# 100kw_dc_motor_controller.net
KiCad netlist of a schematic drawn in EAGLE
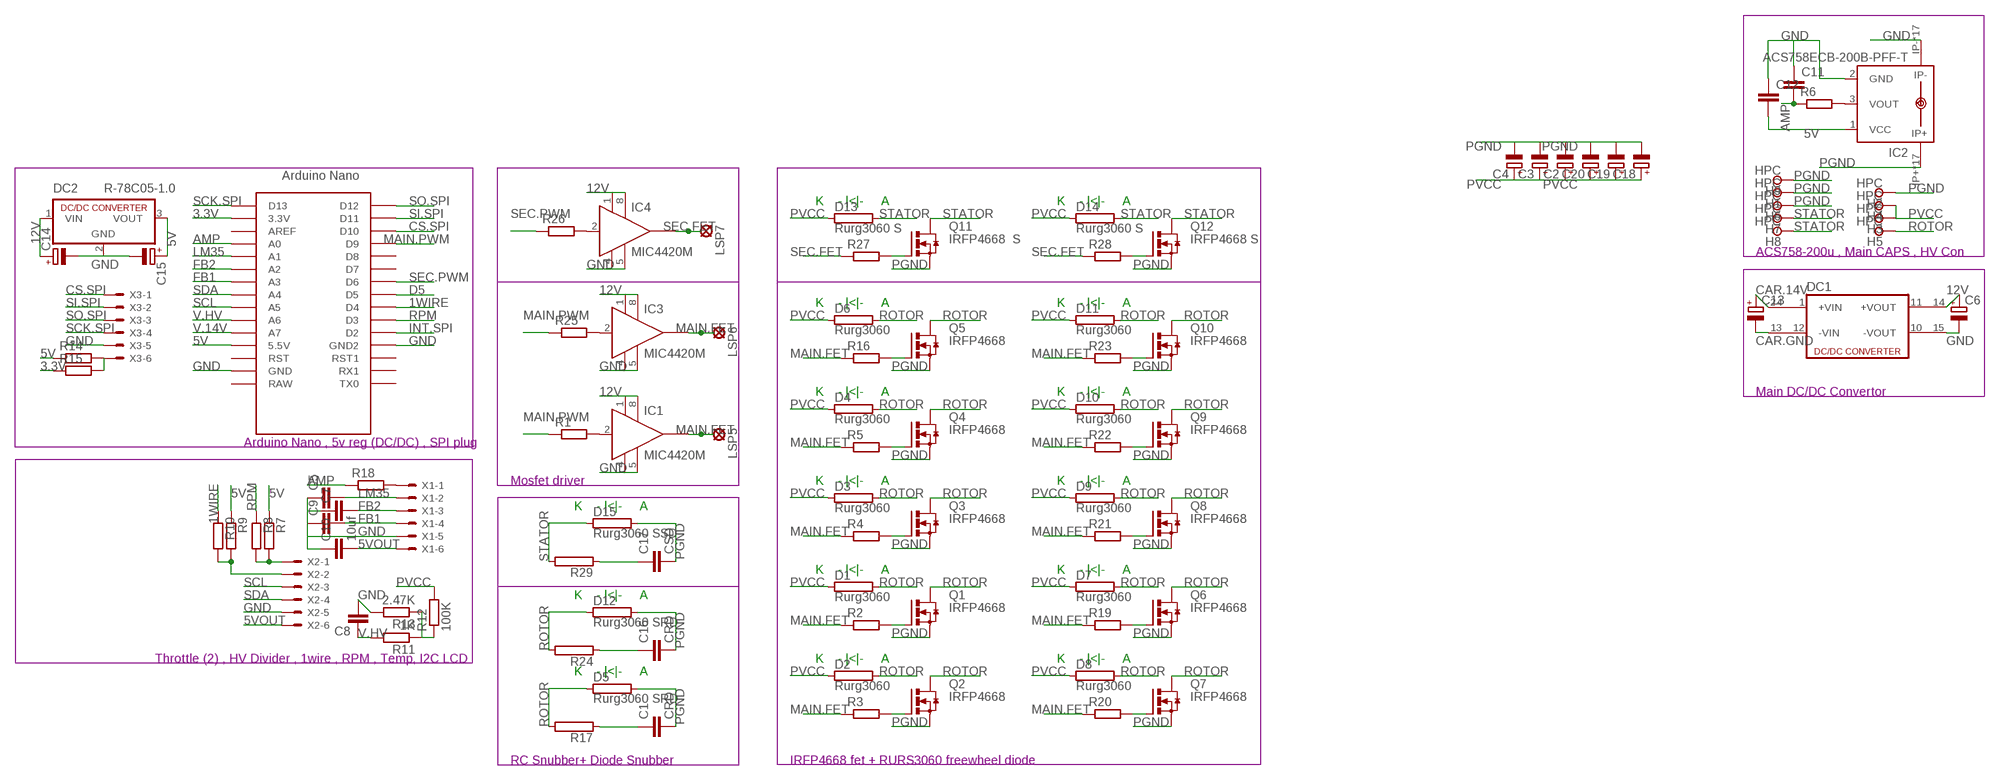
[diagram p0: schematic, sheet 1]

(export (version "E")
  (design (tool "Eeschema 10.0.6"))
  (components
    (comp (ref "C1")
      (value "CRD")
      (footprint "eagle-import:C37.5B20")
      (libsource (lib "eagle-import") (part "C37/20"))
    )
    (comp (ref "C2")
      (value "CPOL-EUE10-35")
      (footprint "eagle-import:EB35D")
      (libsource (lib "eagle-import") (part "CPOL-EUE10-35"))
    )
    (comp (ref "C3")
      (value "CPOL-EUE10-35")
      (footprint "eagle-import:EB35D")
      (libsource (lib "eagle-import") (part "CPOL-EUE10-35"))
    )
    (comp (ref "C4")
      (value "CPOL-EUE10-35")
      (footprint "eagle-import:EB35D")
      (libsource (lib "eagle-import") (part "CPOL-EUE10-35"))
    )
    (comp (ref "C5")
      (value "C-EUC1206")
      (footprint "eagle-import:C1206")
      (libsource (lib "eagle-import") (part "C-EUC1206"))
    )
    (comp (ref "C6")
      (value "CPOL-EUE3.5-10")
      (footprint "eagle-import:E3,5-10")
      (libsource (lib "eagle-import") (part "CPOL-EUE3.5-10"))
    )
    (comp (ref "C7")
      (value "C-EUC1206")
      (footprint "eagle-import:C1206")
      (libsource (lib "eagle-import") (part "C-EUC1206"))
    )
    (comp (ref "C8")
      (value "C-EUC1206")
      (footprint "eagle-import:C1206")
      (libsource (lib "eagle-import") (part "C-EUC1206"))
    )
    (comp (ref "C9")
      (value "C-EUC1206")
      (footprint "eagle-import:C1206")
      (libsource (lib "eagle-import") (part "C-EUC1206"))
    )
    (comp (ref "C10")
      (value "10uf")
      (footprint "eagle-import:C1812")
      (libsource (lib "eagle-import") (part "C-EUC1812"))
    )
    (comp (ref "C11")
      (value "C-EUC1206")
      (footprint "eagle-import:C1206")
      (libsource (lib "eagle-import") (part "C-EUC1206"))
    )
    (comp (ref "C12")
      (value "C-EUC1206")
      (footprint "eagle-import:C1206")
      (libsource (lib "eagle-import") (part "C-EUC1206"))
    )
    (comp (ref "C13")
      (value "CPOL-EUE3.5-10")
      (footprint "eagle-import:E3,5-10")
      (libsource (lib "eagle-import") (part "CPOL-EUE3.5-10"))
    )
    (comp (ref "C14")
      (value "CPOL-EUD/7343-31W")
      (footprint "eagle-import:D_7343-31W")
      (libsource (lib "eagle-import") (part "CPOL-EUD/7343-31W"))
    )
    (comp (ref "C15")
      (value "CPOL-EUD/7343-31W")
      (footprint "eagle-import:D_7343-31W")
      (libsource (lib "eagle-import") (part "CPOL-EUD/7343-31W"))
    )
    (comp (ref "C16")
      (value "CRD")
      (footprint "eagle-import:C37.5B20")
      (libsource (lib "eagle-import") (part "C37/20"))
    )
    (comp (ref "C17")
      (value "CSD")
      (footprint "eagle-import:C37.5B20")
      (libsource (lib "eagle-import") (part "C37/20"))
    )
    (comp (ref "C18")
      (value "CPOL-EUE10-35")
      (footprint "eagle-import:EB35D")
      (libsource (lib "eagle-import") (part "CPOL-EUE10-35"))
    )
    (comp (ref "C19")
      (value "CPOL-EUE10-35")
      (footprint "eagle-import:EB35D")
      (libsource (lib "eagle-import") (part "CPOL-EUE10-35"))
    )
    (comp (ref "C20")
      (value "CPOL-EUE10-35")
      (footprint "eagle-import:EB35D")
      (libsource (lib "eagle-import") (part "CPOL-EUE10-35"))
    )
    (comp (ref "D1")
      (value "Rurg3060")
      (footprint "eagle-import:TO-247-2H")
      (libsource (lib "eagle-import") (part "RMG100-H"))
    )
    (comp (ref "D2")
      (value "Rurg3060")
      (footprint "eagle-import:TO-247-2H")
      (libsource (lib "eagle-import") (part "RMG100-H"))
    )
    (comp (ref "D3")
      (value "Rurg3060")
      (footprint "eagle-import:TO-247-2H")
      (libsource (lib "eagle-import") (part "RMG100-H"))
    )
    (comp (ref "D4")
      (value "Rurg3060")
      (footprint "eagle-import:TO-247-2H")
      (libsource (lib "eagle-import") (part "RMG100-H"))
    )
    (comp (ref "D5")
      (value "Rurg3060 SRD")
      (footprint "eagle-import:TO-247-2V")
      (libsource (lib "eagle-import") (part "RMG100-V"))
    )
    (comp (ref "D6")
      (value "Rurg3060")
      (footprint "eagle-import:TO-247-2H")
      (libsource (lib "eagle-import") (part "RMG100-H"))
    )
    (comp (ref "D7")
      (value "Rurg3060")
      (footprint "eagle-import:TO-247-2H")
      (libsource (lib "eagle-import") (part "RMG100-H"))
    )
    (comp (ref "D8")
      (value "Rurg3060")
      (footprint "eagle-import:TO-247-2H")
      (libsource (lib "eagle-import") (part "RMG100-H"))
    )
    (comp (ref "D9")
      (value "Rurg3060")
      (footprint "eagle-import:TO-247-2H")
      (libsource (lib "eagle-import") (part "RMG100-H"))
    )
    (comp (ref "D10")
      (value "Rurg3060")
      (footprint "eagle-import:TO-247-2H")
      (libsource (lib "eagle-import") (part "RMG100-H"))
    )
    (comp (ref "D11")
      (value "Rurg3060")
      (footprint "eagle-import:TO-247-2H")
      (libsource (lib "eagle-import") (part "RMG100-H"))
    )
    (comp (ref "D12")
      (value "Rurg3060 SRD")
      (footprint "eagle-import:TO-247-2V")
      (libsource (lib "eagle-import") (part "RMG100-V"))
    )
    (comp (ref "D13")
      (value "Rurg3060 S")
      (footprint "eagle-import:TO-247-2H")
      (libsource (lib "eagle-import") (part "RMG100-H"))
    )
    (comp (ref "D14")
      (value "Rurg3060 S")
      (footprint "eagle-import:TO-247-2H")
      (libsource (lib "eagle-import") (part "RMG100-H"))
    )
    (comp (ref "D15")
      (value "Rurg3060 SSD")
      (footprint "eagle-import:TO-247-2V")
      (libsource (lib "eagle-import") (part "RMG100-V"))
    )
    (comp (ref "DC1")
      (value "DCW1U")
      (footprint "eagle-import:DCW")
      (libsource (lib "eagle-import") (part "DCW1U"))
    )
    (comp (ref "DC2")
      (value "R-78C05-1.0")
      (footprint "eagle-import:SIP3")
      (libsource (lib "eagle-import") (part "R-78C-1.03.3"))
    )
    (comp (ref "H1")
      (value "HPC")
      (footprint "eagle-import:PAD_0.2500")
      (libsource (lib "eagle-import") (part "SPECIAL_DRILL_0.2500"))
    )
    (comp (ref "H2")
      (value "HPC")
      (footprint "eagle-import:PAD_0.2500")
      (libsource (lib "eagle-import") (part "SPECIAL_DRILL_0.2500"))
    )
    (comp (ref "H3")
      (value "HPC")
      (footprint "eagle-import:PAD_0.2500")
      (libsource (lib "eagle-import") (part "SPECIAL_DRILL_0.2500"))
    )
    (comp (ref "H4")
      (value "HPC")
      (footprint "eagle-import:PAD_0.2500")
      (libsource (lib "eagle-import") (part "SPECIAL_DRILL_0.2500"))
    )
    (comp (ref "H5")
      (value "HPC")
      (footprint "eagle-import:PAD_0.2500")
      (libsource (lib "eagle-import") (part "SPECIAL_DRILL_0.2500"))
    )
    (comp (ref "H6")
      (value "HPC")
      (footprint "eagle-import:PAD_0.2500")
      (libsource (lib "eagle-import") (part "SPECIAL_DRILL_0.2500"))
    )
    (comp (ref "H7")
      (value "HPC")
      (footprint "eagle-import:PAD_0.2500")
      (libsource (lib "eagle-import") (part "SPECIAL_DRILL_0.2500"))
    )
    (comp (ref "H8")
      (value "HPC")
      (footprint "eagle-import:PAD_0.2500")
      (libsource (lib "eagle-import") (part "SPECIAL_DRILL_0.2500"))
    )
    (comp (ref "H9")
      (value "HPC")
      (footprint "eagle-import:PAD_0.2500")
      (libsource (lib "eagle-import") (part "SPECIAL_DRILL_0.2500"))
    )
    (comp (ref "IC1")
      (value "MIC4420M")
      (footprint "eagle-import:SO-08")
      (libsource (lib "eagle-import") (part "MIC4420M"))
    )
    (comp (ref "IC2")
      (value "ACS758ECB-200B-PFF-T")
      (footprint "eagle-import:CB-PFF")
      (libsource (lib "eagle-import") (part "ACS758ECB-200B-PFF-T"))
    )
    (comp (ref "IC3")
      (value "MIC4420M")
      (footprint "eagle-import:SO-08")
      (libsource (lib "eagle-import") (part "MIC4420M"))
    )
    (comp (ref "IC4")
      (value "MIC4420M")
      (footprint "eagle-import:SO-08")
      (libsource (lib "eagle-import") (part "MIC4420M"))
    )
    (comp (ref "LSP5")
      (value "LSP11")
      (footprint "eagle-import:LSP11")
      (libsource (lib "eagle-import") (part "LSP11"))
    )
    (comp (ref "LSP6")
      (value "LSP11")
      (footprint "eagle-import:LSP11")
      (libsource (lib "eagle-import") (part "LSP11"))
    )
    (comp (ref "LSP7")
      (value "LSP11")
      (footprint "eagle-import:LSP11")
      (libsource (lib "eagle-import") (part "LSP11"))
    )
    (comp (ref "Q1")
      (value "IRFP4668")
      (footprint "eagle-import:TO247BH")
      (libsource (lib "eagle-import") (part "IRFP240-H"))
    )
    (comp (ref "Q2")
      (value "IRFP4668")
      (footprint "eagle-import:TO247BH")
      (libsource (lib "eagle-import") (part "IRFP240-H"))
    )
    (comp (ref "Q3")
      (value "IRFP4668")
      (footprint "eagle-import:TO247BH")
      (libsource (lib "eagle-import") (part "IRFP240-H"))
    )
    (comp (ref "Q4")
      (value "IRFP4668")
      (footprint "eagle-import:TO247BH")
      (libsource (lib "eagle-import") (part "IRFP240-H"))
    )
    (comp (ref "Q5")
      (value "IRFP4668")
      (footprint "eagle-import:TO247BH")
      (libsource (lib "eagle-import") (part "IRFP240-H"))
    )
    (comp (ref "Q6")
      (value "IRFP4668")
      (footprint "eagle-import:TO247BH")
      (libsource (lib "eagle-import") (part "IRFP240-H"))
    )
    (comp (ref "Q7")
      (value "IRFP4668")
      (footprint "eagle-import:TO247BH")
      (libsource (lib "eagle-import") (part "IRFP240-H"))
    )
    (comp (ref "Q8")
      (value "IRFP4668")
      (footprint "eagle-import:TO247BH")
      (libsource (lib "eagle-import") (part "IRFP240-H"))
    )
    (comp (ref "Q9")
      (value "IRFP4668")
      (footprint "eagle-import:TO247BH")
      (libsource (lib "eagle-import") (part "IRFP240-H"))
    )
    (comp (ref "Q10")
      (value "IRFP4668")
      (footprint "eagle-import:TO247BH")
      (libsource (lib "eagle-import") (part "IRFP240-H"))
    )
    (comp (ref "Q11")
      (value "IRFP4668 S")
      (footprint "eagle-import:TO247BH")
      (libsource (lib "eagle-import") (part "IRFP240-H"))
    )
    (comp (ref "Q12")
      (value "IRFP4668 S")
      (footprint "eagle-import:TO247BH")
      (libsource (lib "eagle-import") (part "IRFP240-H"))
    )
    (comp (ref "R1")
      (value "R-EU_R1206")
      (footprint "eagle-import:R1206")
      (libsource (lib "eagle-import") (part "R-EU_R1206"))
    )
    (comp (ref "R2")
      (value "R-EU_M5923")
      (footprint "eagle-import:M5923")
      (libsource (lib "eagle-import") (part "R-EU_M5923"))
    )
    (comp (ref "R3")
      (value "R-EU_M5923")
      (footprint "eagle-import:M5923")
      (libsource (lib "eagle-import") (part "R-EU_M5923"))
    )
    (comp (ref "R4")
      (value "R-EU_M5923")
      (footprint "eagle-import:M5923")
      (libsource (lib "eagle-import") (part "R-EU_M5923"))
    )
    (comp (ref "R5")
      (value "R-EU_M5923")
      (footprint "eagle-import:M5923")
      (libsource (lib "eagle-import") (part "R-EU_M5923"))
    )
    (comp (ref "R6")
      (value "R-EU_R1206")
      (footprint "eagle-import:R1206")
      (libsource (lib "eagle-import") (part "R-EU_R1206"))
    )
    (comp (ref "R7")
      (value "R-EU_R1206")
      (footprint "eagle-import:R1206")
      (libsource (lib "eagle-import") (part "R-EU_R1206"))
    )
    (comp (ref "R8")
      (value "R-EU_R1206")
      (footprint "eagle-import:R1206")
      (libsource (lib "eagle-import") (part "R-EU_R1206"))
    )
    (comp (ref "R9")
      (value "R-EU_R1206")
      (footprint "eagle-import:R1206")
      (libsource (lib "eagle-import") (part "R-EU_R1206"))
    )
    (comp (ref "R10")
      (value "R-EU_R1206")
      (footprint "eagle-import:R1206")
      (libsource (lib "eagle-import") (part "R-EU_R1206"))
    )
    (comp (ref "R11")
      (value "1K")
      (footprint "eagle-import:R1206")
      (libsource (lib "eagle-import") (part "R-EU_R1206"))
    )
    (comp (ref "R12")
      (value "100K")
      (footprint "eagle-import:R1206")
      (libsource (lib "eagle-import") (part "R-EU_R1206"))
    )
    (comp (ref "R13")
      (value "2.47K")
      (footprint "eagle-import:R1206")
      (libsource (lib "eagle-import") (part "R-EU_R1206"))
    )
    (comp (ref "R14")
      (value "R-EU_R1206")
      (footprint "eagle-import:R1206")
      (libsource (lib "eagle-import") (part "R-EU_R1206"))
    )
    (comp (ref "R15")
      (value "R-EU_R1206")
      (footprint "eagle-import:R1206")
      (libsource (lib "eagle-import") (part "R-EU_R1206"))
    )
    (comp (ref "R16")
      (value "R-EU_M5923")
      (footprint "eagle-import:M5923")
      (libsource (lib "eagle-import") (part "R-EU_M5923"))
    )
    (comp (ref "R17")
      (value "RKH208-8R")
      (footprint "eagle-import:KH208R-8")
      (libsource (lib "eagle-import") (part "RKH208-8R"))
    )
    (comp (ref "R18")
      (value "R-EU_R1206")
      (footprint "eagle-import:R1206")
      (libsource (lib "eagle-import") (part "R-EU_R1206"))
    )
    (comp (ref "R19")
      (value "R-EU_M5923")
      (footprint "eagle-import:M5923")
      (libsource (lib "eagle-import") (part "R-EU_M5923"))
    )
    (comp (ref "R20")
      (value "R-EU_M5923")
      (footprint "eagle-import:M5923")
      (libsource (lib "eagle-import") (part "R-EU_M5923"))
    )
    (comp (ref "R21")
      (value "R-EU_M5923")
      (footprint "eagle-import:M5923")
      (libsource (lib "eagle-import") (part "R-EU_M5923"))
    )
    (comp (ref "R22")
      (value "R-EU_M5923")
      (footprint "eagle-import:M5923")
      (libsource (lib "eagle-import") (part "R-EU_M5923"))
    )
    (comp (ref "R23")
      (value "R-EU_M5923")
      (footprint "eagle-import:M5923")
      (libsource (lib "eagle-import") (part "R-EU_M5923"))
    )
    (comp (ref "R24")
      (value "RKH208-8R")
      (footprint "eagle-import:KH208R-8")
      (libsource (lib "eagle-import") (part "RKH208-8R"))
    )
    (comp (ref "R25")
      (value "R-EU_R1206")
      (footprint "eagle-import:R1206")
      (libsource (lib "eagle-import") (part "R-EU_R1206"))
    )
    (comp (ref "R26")
      (value "R-EU_R1206")
      (footprint "eagle-import:R1206")
      (libsource (lib "eagle-import") (part "R-EU_R1206"))
    )
    (comp (ref "R27")
      (value "R-EU_M5923")
      (footprint "eagle-import:M5923")
      (libsource (lib "eagle-import") (part "R-EU_M5923"))
    )
    (comp (ref "R28")
      (value "R-EU_M5923")
      (footprint "eagle-import:M5923")
      (libsource (lib "eagle-import") (part "R-EU_M5923"))
    )
    (comp (ref "R29")
      (value "RKH208-8R")
      (footprint "eagle-import:KH208R-8")
      (libsource (lib "eagle-import") (part "RKH208-8R"))
    )
    (comp (ref "U$1")
      (value "NANO")
      (footprint "eagle-import:NANO")
      (libsource (lib "eagle-import") (part "NANO"))
    )
    (comp (ref "X1")
      (value "22-23-2061")
      (footprint "eagle-import:22-23-2061")
      (fields (field (name "MF") "MOLEX"))
      (libsource (lib "eagle-import") (part "22-23-2061"))
    )
    (comp (ref "X2")
      (value "22-23-2061")
      (footprint "eagle-import:22-23-2061")
      (fields (field (name "MF") "MOLEX"))
      (libsource (lib "eagle-import") (part "22-23-2061"))
    )
    (comp (ref "X3")
      (value "22-23-2061")
      (footprint "eagle-import:22-23-2061")
      (fields (field (name "MF") "MOLEX"))
      (libsource (lib "eagle-import") (part "22-23-2061"))
    )
  )
  (nets
    (net (code "1") (name "/1WIRE") (class "Default")
      (node (ref "R10") (pin "1") (pinfunction "1_1") (pintype "passive"))
      (node (ref "U$1") (pin "D4") (pinfunction "D4_D4") (pintype "bidirectional"))
    )
    (net (code "2") (name "/3.3V") (class "Default")
      (node (ref "R15") (pin "1") (pinfunction "1_1") (pintype "passive"))
      (node (ref "U$1") (pin "3.3V") (pinfunction "3.3V_3.3V") (pintype "bidirectional"))
    )
    (net (code "3") (name "/5V") (class "Default")
      (node (ref "C12") (pin "2") (pinfunction "2_2") (pintype "passive"))
      (node (ref "C15") (pin "+") (pinfunction "+_+") (pintype "passive"))
      (node (ref "DC2") (pin "3") (pinfunction "VOUT_3") (pintype "passive"))
      (node (ref "IC2") (pin "1") (pinfunction "VCC_1") (pintype "power_in"))
      (node (ref "R14") (pin "1") (pinfunction "1_1") (pintype "passive"))
      (node (ref "R7") (pin "1") (pinfunction "1_1") (pintype "passive"))
      (node (ref "R9") (pin "1") (pinfunction "1_1") (pintype "passive"))
      (node (ref "U$1") (pin "5V") (pinfunction "5.5V_5V") (pintype "bidirectional"))
    )
    (net (code "4") (name "/5VOUT") (class "Default")
      (node (ref "C10") (pin "2") (pinfunction "2_2") (pintype "passive"))
      (node (ref "X1") (pin "6") (pinfunction "S_6") (pintype "passive"))
      (node (ref "X2") (pin "6") (pinfunction "S_6") (pintype "passive"))
    )
    (net (code "5") (name "/12V") (class "Default")
      (node (ref "C14") (pin "+") (pinfunction "+_+") (pintype "passive"))
      (node (ref "C6") (pin "+") (pinfunction "+_+") (pintype "passive"))
      (node (ref "DC1") (pin "14") (pinfunction "+VOUT1_14") (pintype "passive"))
      (node (ref "DC2") (pin "1") (pinfunction "VIN_1") (pintype "passive"))
      (node (ref "IC1") (pin "1") (pinfunction "VS_1") (pintype "power_in"))
      (node (ref "IC1") (pin "8") (pinfunction "VS1_8") (pintype "power_in"))
      (node (ref "IC3") (pin "1") (pinfunction "VS_1") (pintype "power_in"))
      (node (ref "IC3") (pin "8") (pinfunction "VS1_8") (pintype "power_in"))
      (node (ref "IC4") (pin "1") (pinfunction "VS_1") (pintype "power_in"))
      (node (ref "IC4") (pin "8") (pinfunction "VS1_8") (pintype "power_in"))
    )
    (net (code "6") (name "/AMP") (class "Default")
      (node (ref "C11") (pin "2") (pinfunction "2_2") (pintype "passive"))
      (node (ref "R18") (pin "1") (pinfunction "1_1") (pintype "passive"))
      (node (ref "R6") (pin "1") (pinfunction "1_1") (pintype "passive"))
      (node (ref "U$1") (pin "A0") (pinfunction "A0_A0") (pintype "bidirectional"))
    )
    (net (code "7") (name "/CAR.14V") (class "Default")
      (node (ref "C13") (pin "+") (pinfunction "+_+") (pintype "passive"))
      (node (ref "DC1") (pin "24") (pinfunction "+VIN1_24") (pintype "passive"))
    )
    (net (code "8") (name "/CAR.GND") (class "Default")
      (node (ref "C13") (pin "-") (pinfunction "-_-") (pintype "passive"))
      (node (ref "DC1") (pin "13") (pinfunction "-VIN1_13") (pintype "passive"))
    )
    (net (code "9") (name "/CS.SPI") (class "Default")
      (node (ref "U$1") (pin "D10") (pinfunction "D10_D10") (pintype "bidirectional"))
      (node (ref "X3") (pin "1") (pinfunction "S_1") (pintype "passive"))
    )
    (net (code "10") (name "/D5") (class "Default")
      (node (ref "U$1") (pin "D5") (pinfunction "D5_D5") (pintype "bidirectional"))
    )
    (net (code "11") (name "/FB1") (class "Default")
      (node (ref "C9") (pin "2") (pinfunction "2_2") (pintype "passive"))
      (node (ref "U$1") (pin "A3") (pinfunction "A3_A3") (pintype "bidirectional"))
      (node (ref "X1") (pin "4") (pinfunction "S_4") (pintype "passive"))
    )
    (net (code "12") (name "/FB2") (class "Default")
      (node (ref "C7") (pin "2") (pinfunction "2_2") (pintype "passive"))
      (node (ref "U$1") (pin "A2") (pinfunction "A2_A2") (pintype "bidirectional"))
      (node (ref "X1") (pin "3") (pinfunction "S_3") (pintype "passive"))
    )
    (net (code "13") (name "/GND") (class "Default")
      (node (ref "C10") (pin "1") (pinfunction "1_1") (pintype "passive"))
      (node (ref "C11") (pin "1") (pinfunction "1_1") (pintype "passive"))
      (node (ref "C12") (pin "1") (pinfunction "1_1") (pintype "passive"))
      (node (ref "C14") (pin "-") (pinfunction "-_-") (pintype "passive"))
      (node (ref "C15") (pin "-") (pinfunction "-_-") (pintype "passive"))
      (node (ref "C5") (pin "1") (pinfunction "1_1") (pintype "passive"))
      (node (ref "C6") (pin "-") (pinfunction "-_-") (pintype "passive"))
      (node (ref "C7") (pin "1") (pinfunction "1_1") (pintype "passive"))
      (node (ref "C8") (pin "2") (pinfunction "2_2") (pintype "passive"))
      (node (ref "C9") (pin "1") (pinfunction "1_1") (pintype "passive"))
      (node (ref "DC1") (pin "15") (pinfunction "-VOUT1_15") (pintype "passive"))
      (node (ref "DC2") (pin "2") (pinfunction "GND_2") (pintype "passive"))
      (node (ref "IC1") (pin "4") (pinfunction "GND_4") (pintype "power_in"))
      (node (ref "IC1") (pin "5") (pinfunction "GND1_5") (pintype "power_in"))
      (node (ref "IC2") (pin "2") (pinfunction "GND_2") (pintype "power_in"))
      (node (ref "IC2") (pin "IP-") (pinfunction "IP-_IP-") (pintype "passive"))
      (node (ref "IC2") (pin "IP-@10") (pinfunction "IP-_IP-@10") (pintype "passive"))
      (node (ref "IC2") (pin "IP-@11") (pinfunction "IP-_IP-@11") (pintype "passive"))
      (node (ref "IC2") (pin "IP-@12") (pinfunction "IP-_IP-@12") (pintype "passive"))
      (node (ref "IC2") (pin "IP-@13") (pinfunction "IP-_IP-@13") (pintype "passive"))
      (node (ref "IC2") (pin "IP-@14") (pinfunction "IP-_IP-@14") (pintype "passive"))
      (node (ref "IC2") (pin "IP-@15") (pinfunction "IP-_IP-@15") (pintype "passive"))
      (node (ref "IC2") (pin "IP-@16") (pinfunction "IP-_IP-@16") (pintype "passive"))
      (node (ref "IC2") (pin "IP-@17") (pinfunction "IP-_IP-@17") (pintype "passive"))
      (node (ref "IC2") (pin "IP-@2") (pinfunction "IP-_IP-@2") (pintype "passive"))
      (node (ref "IC2") (pin "IP-@3") (pinfunction "IP-_IP-@3") (pintype "passive"))
      (node (ref "IC2") (pin "IP-@4") (pinfunction "IP-_IP-@4") (pintype "passive"))
      (node (ref "IC2") (pin "IP-@5") (pinfunction "IP-_IP-@5") (pintype "passive"))
      (node (ref "IC2") (pin "IP-@6") (pinfunction "IP-_IP-@6") (pintype "passive"))
      (node (ref "IC2") (pin "IP-@7") (pinfunction "IP-_IP-@7") (pintype "passive"))
      (node (ref "IC2") (pin "IP-@8") (pinfunction "IP-_IP-@8") (pintype "passive"))
      (node (ref "IC2") (pin "IP-@9") (pinfunction "IP-_IP-@9") (pintype "passive"))
      (node (ref "IC3") (pin "4") (pinfunction "GND_4") (pintype "power_in"))
      (node (ref "IC3") (pin "5") (pinfunction "GND1_5") (pintype "power_in"))
      (node (ref "IC4") (pin "4") (pinfunction "GND_4") (pintype "power_in"))
      (node (ref "IC4") (pin "5") (pinfunction "GND1_5") (pintype "power_in"))
      (node (ref "R13") (pin "2") (pinfunction "2_2") (pintype "passive"))
      (node (ref "U$1") (pin "GND") (pinfunction "GND_GND") (pintype "bidirectional"))
      (node (ref "U$1") (pin "GND1") (pinfunction "GND2_GND1") (pintype "bidirectional"))
      (node (ref "X1") (pin "5") (pinfunction "S_5") (pintype "passive"))
      (node (ref "X2") (pin "5") (pinfunction "S_5") (pintype "passive"))
      (node (ref "X3") (pin "5") (pinfunction "S_5") (pintype "passive"))
    )
    (net (code "14") (name "/INT.SPI") (class "Default")
      (node (ref "U$1") (pin "D2") (pinfunction "D2_D2") (pintype "bidirectional"))
    )
    (net (code "15") (name "/LM35") (class "Default")
      (node (ref "C5") (pin "2") (pinfunction "2_2") (pintype "passive"))
      (node (ref "U$1") (pin "A1") (pinfunction "A1_A1") (pintype "bidirectional"))
      (node (ref "X1") (pin "2") (pinfunction "S_2") (pintype "passive"))
    )
    (net (code "16") (name "/MAIN.FET") (class "Default")
      (node (ref "IC1") (pin "6") (pinfunction "OUT_6") (pintype "passive"))
      (node (ref "IC3") (pin "6") (pinfunction "OUT_6") (pintype "passive"))
      (node (ref "LSP5") (pin "MP") (pinfunction "MP_MP") (pintype "passive"))
      (node (ref "LSP6") (pin "MP") (pinfunction "MP_MP") (pintype "passive"))
      (node (ref "R16") (pin "1") (pinfunction "1_1") (pintype "passive"))
      (node (ref "R19") (pin "1") (pinfunction "1_1") (pintype "passive"))
      (node (ref "R2") (pin "1") (pinfunction "1_1") (pintype "passive"))
      (node (ref "R20") (pin "1") (pinfunction "1_1") (pintype "passive"))
      (node (ref "R21") (pin "1") (pinfunction "1_1") (pintype "passive"))
      (node (ref "R22") (pin "1") (pinfunction "1_1") (pintype "passive"))
      (node (ref "R23") (pin "1") (pinfunction "1_1") (pintype "passive"))
      (node (ref "R3") (pin "1") (pinfunction "1_1") (pintype "passive"))
      (node (ref "R4") (pin "1") (pinfunction "1_1") (pintype "passive"))
      (node (ref "R5") (pin "1") (pinfunction "1_1") (pintype "passive"))
    )
    (net (code "17") (name "/MAIN.PWM") (class "Default")
      (node (ref "R1") (pin "1") (pinfunction "1_1") (pintype "passive"))
      (node (ref "R25") (pin "1") (pinfunction "1_1") (pintype "passive"))
      (node (ref "U$1") (pin "D9") (pinfunction "D9_D9") (pintype "bidirectional"))
    )
    (net (code "18") (name "/PGND") (class "Default")
      (node (ref "C1") (pin "2") (pinfunction "2_2") (pintype "passive"))
      (node (ref "C16") (pin "2") (pinfunction "2_2") (pintype "passive"))
      (node (ref "C17") (pin "2") (pinfunction "2_2") (pintype "passive"))
      (node (ref "C18") (pin "-") (pinfunction "-_-") (pintype "passive"))
      (node (ref "C19") (pin "-") (pinfunction "-_-") (pintype "passive"))
      (node (ref "C2") (pin "-") (pinfunction "-_-") (pintype "passive"))
      (node (ref "C20") (pin "-") (pinfunction "-_-") (pintype "passive"))
      (node (ref "C3") (pin "-") (pinfunction "-_-") (pintype "passive"))
      (node (ref "C4") (pin "-") (pinfunction "-_-") (pintype "passive"))
      (node (ref "D12") (pin "2") (pinfunction "2_2") (pintype "passive"))
      (node (ref "D15") (pin "2") (pinfunction "2_2") (pintype "passive"))
      (node (ref "D5") (pin "2") (pinfunction "2_2") (pintype "passive"))
      (node (ref "H1") (pin "1") (pinfunction "1_1") (pintype "passive"))
      (node (ref "H2") (pin "1") (pinfunction "1_1") (pintype "passive"))
      (node (ref "H6") (pin "1") (pinfunction "1_1") (pintype "passive"))
      (node (ref "H9") (pin "1") (pinfunction "1_1") (pintype "passive"))
      (node (ref "IC2") (pin "IP+") (pinfunction "IP+_IP+") (pintype "passive"))
      (node (ref "IC2") (pin "IP+@10") (pinfunction "IP+_IP+@10") (pintype "passive"))
      (node (ref "IC2") (pin "IP+@11") (pinfunction "IP+_IP+@11") (pintype "passive"))
      (node (ref "IC2") (pin "IP+@12") (pinfunction "IP+_IP+@12") (pintype "passive"))
      (node (ref "IC2") (pin "IP+@13") (pinfunction "IP+_IP+@13") (pintype "passive"))
      (node (ref "IC2") (pin "IP+@14") (pinfunction "IP+_IP+@14") (pintype "passive"))
      (node (ref "IC2") (pin "IP+@15") (pinfunction "IP+_IP+@15") (pintype "passive"))
      (node (ref "IC2") (pin "IP+@16") (pinfunction "IP+_IP+@16") (pintype "passive"))
      (node (ref "IC2") (pin "IP+@17") (pinfunction "IP+_IP+@17") (pintype "passive"))
      (node (ref "IC2") (pin "IP+@2") (pinfunction "IP+_IP+@2") (pintype "passive"))
      (node (ref "IC2") (pin "IP+@3") (pinfunction "IP+_IP+@3") (pintype "passive"))
      (node (ref "IC2") (pin "IP+@4") (pinfunction "IP+_IP+@4") (pintype "passive"))
      (node (ref "IC2") (pin "IP+@5") (pinfunction "IP+_IP+@5") (pintype "passive"))
      (node (ref "IC2") (pin "IP+@6") (pinfunction "IP+_IP+@6") (pintype "passive"))
      (node (ref "IC2") (pin "IP+@7") (pinfunction "IP+_IP+@7") (pintype "passive"))
      (node (ref "IC2") (pin "IP+@8") (pinfunction "IP+_IP+@8") (pintype "passive"))
      (node (ref "IC2") (pin "IP+@9") (pinfunction "IP+_IP+@9") (pintype "passive"))
      (node (ref "Q1") (pin "S") (pinfunction "S_S") (pintype "passive"))
      (node (ref "Q10") (pin "S") (pinfunction "S_S") (pintype "passive"))
      (node (ref "Q11") (pin "S") (pinfunction "S_S") (pintype "passive"))
      (node (ref "Q12") (pin "S") (pinfunction "S_S") (pintype "passive"))
      (node (ref "Q2") (pin "S") (pinfunction "S_S") (pintype "passive"))
      (node (ref "Q3") (pin "S") (pinfunction "S_S") (pintype "passive"))
      (node (ref "Q4") (pin "S") (pinfunction "S_S") (pintype "passive"))
      (node (ref "Q5") (pin "S") (pinfunction "S_S") (pintype "passive"))
      (node (ref "Q6") (pin "S") (pinfunction "S_S") (pintype "passive"))
      (node (ref "Q7") (pin "S") (pinfunction "S_S") (pintype "passive"))
      (node (ref "Q8") (pin "S") (pinfunction "S_S") (pintype "passive"))
      (node (ref "Q9") (pin "S") (pinfunction "S_S") (pintype "passive"))
    )
    (net (code "19") (name "/PVCC") (class "Default")
      (node (ref "C18") (pin "+") (pinfunction "+_+") (pintype "passive"))
      (node (ref "C19") (pin "+") (pinfunction "+_+") (pintype "passive"))
      (node (ref "C2") (pin "+") (pinfunction "+_+") (pintype "passive"))
      (node (ref "C20") (pin "+") (pinfunction "+_+") (pintype "passive"))
      (node (ref "C3") (pin "+") (pinfunction "+_+") (pintype "passive"))
      (node (ref "C4") (pin "+") (pinfunction "+_+") (pintype "passive"))
      (node (ref "D1") (pin "1") (pinfunction "1_1") (pintype "passive"))
      (node (ref "D10") (pin "1") (pinfunction "1_1") (pintype "passive"))
      (node (ref "D11") (pin "1") (pinfunction "1_1") (pintype "passive"))
      (node (ref "D13") (pin "1") (pinfunction "1_1") (pintype "passive"))
      (node (ref "D14") (pin "1") (pinfunction "1_1") (pintype "passive"))
      (node (ref "D2") (pin "1") (pinfunction "1_1") (pintype "passive"))
      (node (ref "D3") (pin "1") (pinfunction "1_1") (pintype "passive"))
      (node (ref "D4") (pin "1") (pinfunction "1_1") (pintype "passive"))
      (node (ref "D6") (pin "1") (pinfunction "1_1") (pintype "passive"))
      (node (ref "D7") (pin "1") (pinfunction "1_1") (pintype "passive"))
      (node (ref "D8") (pin "1") (pinfunction "1_1") (pintype "passive"))
      (node (ref "D9") (pin "1") (pinfunction "1_1") (pintype "passive"))
      (node (ref "H3") (pin "1") (pinfunction "1_1") (pintype "passive"))
      (node (ref "H4") (pin "1") (pinfunction "1_1") (pintype "passive"))
      (node (ref "R12") (pin "2") (pinfunction "2_2") (pintype "passive"))
    )
    (net (code "20") (name "/ROTOR") (class "Default")
      (node (ref "D1") (pin "2") (pinfunction "2_2") (pintype "passive"))
      (node (ref "D10") (pin "2") (pinfunction "2_2") (pintype "passive"))
      (node (ref "D11") (pin "2") (pinfunction "2_2") (pintype "passive"))
      (node (ref "D12") (pin "1") (pinfunction "1_1") (pintype "passive"))
      (node (ref "D2") (pin "2") (pinfunction "2_2") (pintype "passive"))
      (node (ref "D3") (pin "2") (pinfunction "2_2") (pintype "passive"))
      (node (ref "D4") (pin "2") (pinfunction "2_2") (pintype "passive"))
      (node (ref "D5") (pin "1") (pinfunction "1_1") (pintype "passive"))
      (node (ref "D6") (pin "2") (pinfunction "2_2") (pintype "passive"))
      (node (ref "D7") (pin "2") (pinfunction "2_2") (pintype "passive"))
      (node (ref "D8") (pin "2") (pinfunction "2_2") (pintype "passive"))
      (node (ref "D9") (pin "2") (pinfunction "2_2") (pintype "passive"))
      (node (ref "H5") (pin "1") (pinfunction "1_1") (pintype "passive"))
      (node (ref "Q1") (pin "D") (pinfunction "D_D") (pintype "passive"))
      (node (ref "Q10") (pin "D") (pinfunction "D_D") (pintype "passive"))
      (node (ref "Q2") (pin "D") (pinfunction "D_D") (pintype "passive"))
      (node (ref "Q3") (pin "D") (pinfunction "D_D") (pintype "passive"))
      (node (ref "Q4") (pin "D") (pinfunction "D_D") (pintype "passive"))
      (node (ref "Q5") (pin "D") (pinfunction "D_D") (pintype "passive"))
      (node (ref "Q6") (pin "D") (pinfunction "D_D") (pintype "passive"))
      (node (ref "Q7") (pin "D") (pinfunction "D_D") (pintype "passive"))
      (node (ref "Q8") (pin "D") (pinfunction "D_D") (pintype "passive"))
      (node (ref "Q9") (pin "D") (pinfunction "D_D") (pintype "passive"))
      (node (ref "R17") (pin "2") (pinfunction "2_2") (pintype "passive"))
      (node (ref "R24") (pin "2") (pinfunction "2_2") (pintype "passive"))
    )
    (net (code "21") (name "/RPM") (class "Default")
      (node (ref "R8") (pin "1") (pinfunction "1_1") (pintype "passive"))
      (node (ref "U$1") (pin "D3") (pinfunction "D3_D3") (pintype "bidirectional"))
    )
    (net (code "22") (name "/SCK.SPI") (class "Default")
      (node (ref "U$1") (pin "D13") (pinfunction "D13_D13") (pintype "bidirectional"))
      (node (ref "X3") (pin "4") (pinfunction "S_4") (pintype "passive"))
    )
    (net (code "23") (name "/SCL") (class "Default")
      (node (ref "U$1") (pin "A5") (pinfunction "A5_A5") (pintype "bidirectional"))
      (node (ref "X2") (pin "3") (pinfunction "S_3") (pintype "passive"))
    )
    (net (code "24") (name "/SDA") (class "Default")
      (node (ref "U$1") (pin "A4") (pinfunction "A4_A4") (pintype "bidirectional"))
      (node (ref "X2") (pin "4") (pinfunction "S_4") (pintype "passive"))
    )
    (net (code "25") (name "/SEC.FET") (class "Default")
      (node (ref "IC4") (pin "6") (pinfunction "OUT_6") (pintype "passive"))
      (node (ref "LSP7") (pin "MP") (pinfunction "MP_MP") (pintype "passive"))
      (node (ref "R27") (pin "1") (pinfunction "1_1") (pintype "passive"))
      (node (ref "R28") (pin "1") (pinfunction "1_1") (pintype "passive"))
    )
    (net (code "26") (name "/SEC.PWM") (class "Default")
      (node (ref "R26") (pin "1") (pinfunction "1_1") (pintype "passive"))
      (node (ref "U$1") (pin "D6") (pinfunction "D6_D6") (pintype "bidirectional"))
    )
    (net (code "27") (name "/SI.SPI") (class "Default")
      (node (ref "U$1") (pin "D11") (pinfunction "D11_D11") (pintype "bidirectional"))
      (node (ref "X3") (pin "2") (pinfunction "S_2") (pintype "passive"))
    )
    (net (code "28") (name "/SO.SPI") (class "Default")
      (node (ref "U$1") (pin "D12") (pinfunction "D12_D12") (pintype "bidirectional"))
      (node (ref "X3") (pin "3") (pinfunction "S_3") (pintype "passive"))
    )
    (net (code "29") (name "/STATOR") (class "Default")
      (node (ref "D13") (pin "2") (pinfunction "2_2") (pintype "passive"))
      (node (ref "D14") (pin "2") (pinfunction "2_2") (pintype "passive"))
      (node (ref "D15") (pin "1") (pinfunction "1_1") (pintype "passive"))
      (node (ref "H7") (pin "1") (pinfunction "1_1") (pintype "passive"))
      (node (ref "H8") (pin "1") (pinfunction "1_1") (pintype "passive"))
      (node (ref "Q11") (pin "D") (pinfunction "D_D") (pintype "passive"))
      (node (ref "Q12") (pin "D") (pinfunction "D_D") (pintype "passive"))
      (node (ref "R29") (pin "2") (pinfunction "2_2") (pintype "passive"))
    )
    (net (code "30") (name "/V.14V") (class "Default")
      (node (ref "U$1") (pin "A7") (pinfunction "A7_A7") (pintype "bidirectional"))
    )
    (net (code "31") (name "/V.HV") (class "Default")
      (node (ref "C8") (pin "1") (pinfunction "1_1") (pintype "passive"))
      (node (ref "R11") (pin "2") (pinfunction "2_2") (pintype "passive"))
      (node (ref "U$1") (pin "A6") (pinfunction "A6_A6") (pintype "bidirectional"))
    )
    (net (code "32") (name "Net-(C1-Pad1)") (class "Default")
      (node (ref "C1") (pin "1") (pinfunction "1_1") (pintype "passive"))
      (node (ref "R17") (pin "1") (pinfunction "1_1") (pintype "passive"))
    )
    (net (code "33") (name "Net-(C16-Pad1)") (class "Default")
      (node (ref "C16") (pin "1") (pinfunction "1_1") (pintype "passive"))
      (node (ref "R24") (pin "1") (pinfunction "1_1") (pintype "passive"))
    )
    (net (code "34") (name "Net-(C17-Pad1)") (class "Default")
      (node (ref "C17") (pin "1") (pinfunction "1_1") (pintype "passive"))
      (node (ref "R29") (pin "1") (pinfunction "1_1") (pintype "passive"))
    )
    (net (code "35") (name "Net-(IC1-IN)") (class "Default")
      (node (ref "IC1") (pin "2") (pinfunction "IN_2") (pintype "input"))
      (node (ref "R1") (pin "2") (pinfunction "2_2") (pintype "passive"))
    )
    (net (code "36") (name "Net-(IC2-VOUT)") (class "Default")
      (node (ref "IC2") (pin "3") (pinfunction "VOUT_3") (pintype "output"))
      (node (ref "R6") (pin "2") (pinfunction "2_2") (pintype "passive"))
    )
    (net (code "37") (name "Net-(IC3-IN)") (class "Default")
      (node (ref "IC3") (pin "2") (pinfunction "IN_2") (pintype "input"))
      (node (ref "R25") (pin "2") (pinfunction "2_2") (pintype "passive"))
    )
    (net (code "38") (name "Net-(IC4-IN)") (class "Default")
      (node (ref "IC4") (pin "2") (pinfunction "IN_2") (pintype "input"))
      (node (ref "R26") (pin "2") (pinfunction "2_2") (pintype "passive"))
    )
    (net (code "39") (name "Net-(Q1-PadG)") (class "Default")
      (node (ref "Q1") (pin "G") (pinfunction "G_G") (pintype "passive"))
      (node (ref "R2") (pin "2") (pinfunction "2_2") (pintype "passive"))
    )
    (net (code "40") (name "Net-(Q2-PadG)") (class "Default")
      (node (ref "Q2") (pin "G") (pinfunction "G_G") (pintype "passive"))
      (node (ref "R3") (pin "2") (pinfunction "2_2") (pintype "passive"))
    )
    (net (code "41") (name "Net-(Q3-PadG)") (class "Default")
      (node (ref "Q3") (pin "G") (pinfunction "G_G") (pintype "passive"))
      (node (ref "R4") (pin "2") (pinfunction "2_2") (pintype "passive"))
    )
    (net (code "42") (name "Net-(Q4-PadG)") (class "Default")
      (node (ref "Q4") (pin "G") (pinfunction "G_G") (pintype "passive"))
      (node (ref "R5") (pin "2") (pinfunction "2_2") (pintype "passive"))
    )
    (net (code "43") (name "Net-(Q5-PadG)") (class "Default")
      (node (ref "Q5") (pin "G") (pinfunction "G_G") (pintype "passive"))
      (node (ref "R16") (pin "2") (pinfunction "2_2") (pintype "passive"))
    )
    (net (code "44") (name "Net-(Q6-PadG)") (class "Default")
      (node (ref "Q6") (pin "G") (pinfunction "G_G") (pintype "passive"))
      (node (ref "R19") (pin "2") (pinfunction "2_2") (pintype "passive"))
    )
    (net (code "45") (name "Net-(Q7-PadG)") (class "Default")
      (node (ref "Q7") (pin "G") (pinfunction "G_G") (pintype "passive"))
      (node (ref "R20") (pin "2") (pinfunction "2_2") (pintype "passive"))
    )
    (net (code "46") (name "Net-(Q8-PadG)") (class "Default")
      (node (ref "Q8") (pin "G") (pinfunction "G_G") (pintype "passive"))
      (node (ref "R21") (pin "2") (pinfunction "2_2") (pintype "passive"))
    )
    (net (code "47") (name "Net-(Q9-PadG)") (class "Default")
      (node (ref "Q9") (pin "G") (pinfunction "G_G") (pintype "passive"))
      (node (ref "R22") (pin "2") (pinfunction "2_2") (pintype "passive"))
    )
    (net (code "48") (name "Net-(Q10-PadG)") (class "Default")
      (node (ref "Q10") (pin "G") (pinfunction "G_G") (pintype "passive"))
      (node (ref "R23") (pin "2") (pinfunction "2_2") (pintype "passive"))
    )
    (net (code "49") (name "Net-(Q11-PadG)") (class "Default")
      (node (ref "Q11") (pin "G") (pinfunction "G_G") (pintype "passive"))
      (node (ref "R27") (pin "2") (pinfunction "2_2") (pintype "passive"))
    )
    (net (code "50") (name "Net-(Q12-PadG)") (class "Default")
      (node (ref "Q12") (pin "G") (pinfunction "G_G") (pintype "passive"))
      (node (ref "R28") (pin "2") (pinfunction "2_2") (pintype "passive"))
    )
    (net (code "51") (name "Net-(R11-Pad1)") (class "Default")
      (node (ref "R11") (pin "1") (pinfunction "1_1") (pintype "passive"))
      (node (ref "R12") (pin "1") (pinfunction "1_1") (pintype "passive"))
      (node (ref "R13") (pin "1") (pinfunction "1_1") (pintype "passive"))
    )
    (net (code "52") (name "Net-(X1A-S)") (class "Default")
      (node (ref "R18") (pin "2") (pinfunction "2_2") (pintype "passive"))
      (node (ref "X1") (pin "1") (pinfunction "S_1") (pintype "passive"))
    )
    (net (code "53") (name "Net-(X2A-S)") (class "Default")
      (node (ref "R7") (pin "2") (pinfunction "2_2") (pintype "passive"))
      (node (ref "R8") (pin "2") (pinfunction "2_2") (pintype "passive"))
      (node (ref "X2") (pin "1") (pinfunction "S_1") (pintype "passive"))
    )
    (net (code "54") (name "Net-(X2B-S)") (class "Default")
      (node (ref "R10") (pin "2") (pinfunction "2_2") (pintype "passive"))
      (node (ref "R9") (pin "2") (pinfunction "2_2") (pintype "passive"))
      (node (ref "X2") (pin "2") (pinfunction "S_2") (pintype "passive"))
    )
    (net (code "55") (name "Net-(X3F-S)") (class "Default")
      (node (ref "R14") (pin "2") (pinfunction "2_2") (pintype "passive"))
      (node (ref "R15") (pin "2") (pinfunction "2_2") (pintype "passive"))
      (node (ref "X3") (pin "6") (pinfunction "S_6") (pintype "passive"))
    )
    (net (code "56") (name "unconnected-(DC1-+VIN-Pad1)") (class "Default")
      (node (ref "DC1") (pin "1") (pinfunction "+VIN_1") (pintype "passive"))
    )
    (net (code "57") (name "unconnected-(DC1-+VOUT-Pad11)") (class "Default")
      (node (ref "DC1") (pin "11") (pinfunction "+VOUT_11") (pintype "passive"))
    )
    (net (code "58") (name "unconnected-(DC1--VIN-Pad12)") (class "Default")
      (node (ref "DC1") (pin "12") (pinfunction "-VIN_12") (pintype "passive"))
    )
    (net (code "59") (name "unconnected-(DC1--VOUT-Pad10)") (class "Default")
      (node (ref "DC1") (pin "10") (pinfunction "-VOUT_10") (pintype "passive"))
    )
    (net (code "60") (name "unconnected-(IC1-OUT-Pad7)") (class "Default")
      (node (ref "IC1") (pin "7") (pinfunction "OUT_7") (pintype "passive"))
    )
    (net (code "61") (name "unconnected-(IC3-OUT-Pad7)") (class "Default")
      (node (ref "IC3") (pin "7") (pinfunction "OUT_7") (pintype "passive"))
    )
    (net (code "62") (name "unconnected-(IC4-OUT-Pad7)") (class "Default")
      (node (ref "IC4") (pin "7") (pinfunction "OUT_7") (pintype "passive"))
    )
    (net (code "63") (name "unconnected-(U$1-PadAREF)") (class "Default")
      (node (ref "U$1") (pin "AREF") (pinfunction "AREF_AREF") (pintype "bidirectional"))
    )
    (net (code "64") (name "unconnected-(U$1-PadD7)") (class "Default")
      (node (ref "U$1") (pin "D7") (pinfunction "D7_D7") (pintype "bidirectional"))
    )
    (net (code "65") (name "unconnected-(U$1-PadD8)") (class "Default")
      (node (ref "U$1") (pin "D8") (pinfunction "D8_D8") (pintype "bidirectional"))
    )
    (net (code "66") (name "unconnected-(U$1-PadICSP1)") (class "Default")
      (node (ref "U$1") (pin "ICSP1") (pinfunction "ICSP1_ICSP1") (pintype "bidirectional"))
    )
    (net (code "67") (name "unconnected-(U$1-PadICSP2)") (class "Default")
      (node (ref "U$1") (pin "ICSP2") (pinfunction "ICSP2_ICSP2") (pintype "bidirectional"))
    )
    (net (code "68") (name "unconnected-(U$1-PadICSP3)") (class "Default")
      (node (ref "U$1") (pin "ICSP3") (pinfunction "ICSP3_ICSP3") (pintype "bidirectional"))
    )
    (net (code "69") (name "unconnected-(U$1-PadICSP4)") (class "Default")
      (node (ref "U$1") (pin "ICSP4") (pinfunction "ICSP4_ICSP4") (pintype "bidirectional"))
    )
    (net (code "70") (name "unconnected-(U$1-PadICSP5)") (class "Default")
      (node (ref "U$1") (pin "ICSP5") (pinfunction "ICSP5_ICSP5") (pintype "bidirectional"))
    )
    (net (code "71") (name "unconnected-(U$1-PadICSP6)") (class "Default")
      (node (ref "U$1") (pin "ICSP6") (pinfunction "ICSP6_ICSP6") (pintype "bidirectional"))
    )
    (net (code "72") (name "unconnected-(U$1-PadRAW)") (class "Default")
      (node (ref "U$1") (pin "RAW") (pinfunction "RAW_RAW") (pintype "bidirectional"))
    )
    (net (code "73") (name "unconnected-(U$1-PadRST)") (class "Default")
      (node (ref "U$1") (pin "RST") (pinfunction "RST_RST") (pintype "bidirectional"))
    )
    (net (code "74") (name "unconnected-(U$1-PadRST1)") (class "Default")
      (node (ref "U$1") (pin "RST1") (pinfunction "RST1_RST1") (pintype "bidirectional"))
    )
    (net (code "75") (name "unconnected-(U$1-PadRX1)") (class "Default")
      (node (ref "U$1") (pin "RX1") (pinfunction "RX1_RX1") (pintype "bidirectional"))
    )
    (net (code "76") (name "unconnected-(U$1-PadTX0)") (class "Default")
      (node (ref "U$1") (pin "TX0") (pinfunction "TX0_TX0") (pintype "bidirectional"))
    )
  )
)
